# 07_SDDADC.net
KiCad netlist of a schematic drawn in Altium Designer
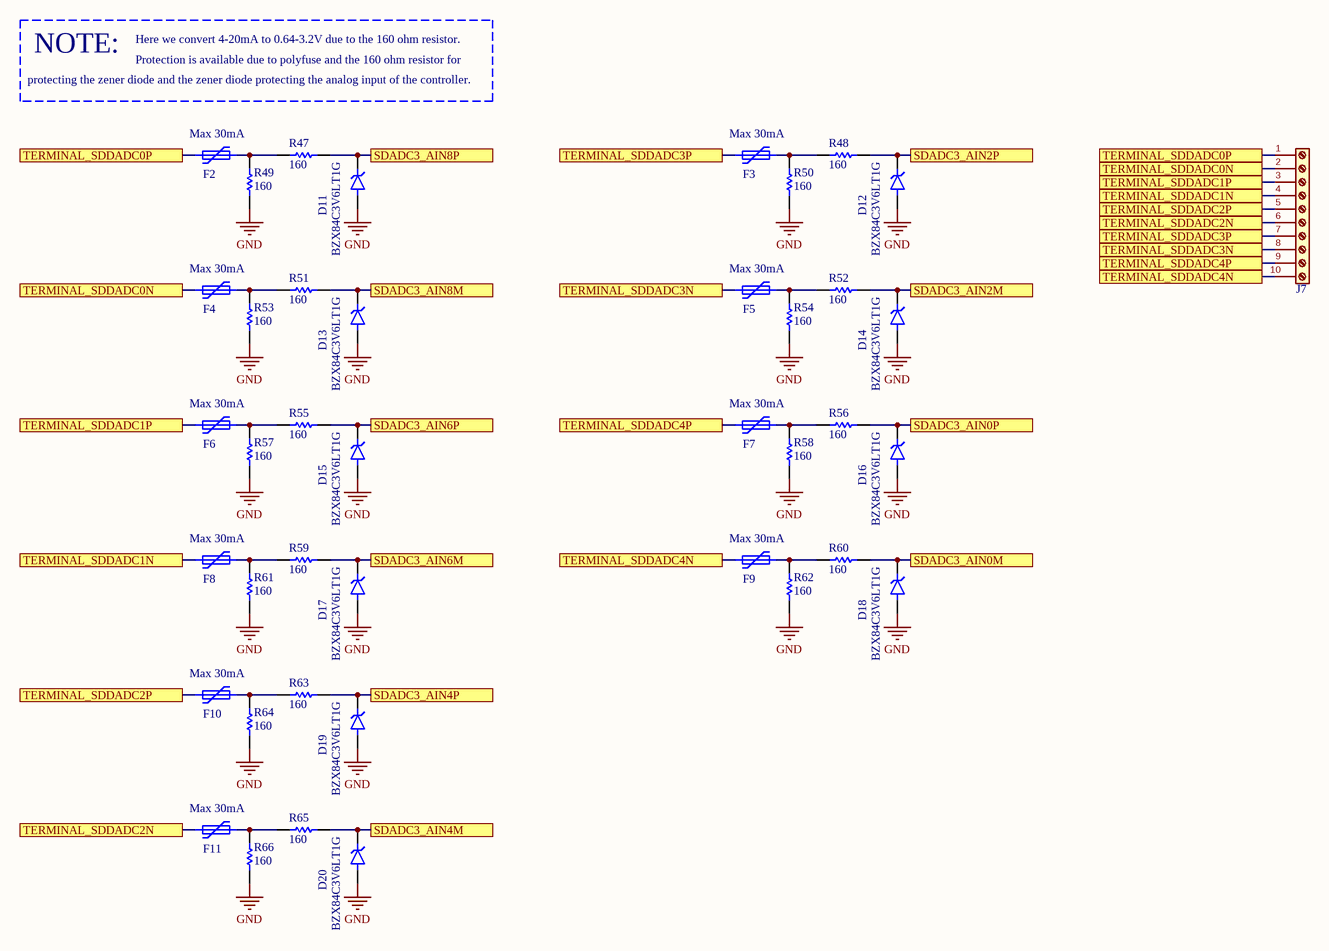
[diagram p0: 07_SDDADC.SchDoc]

(export (version "E")
  (design (tool "Eeschema 10.0.6"))
  (components
    (comp (ref "D11")
      (value "BZX84C3V6LT1G")
      (footprint "SOT95P240X111-3N")
      (fields (field (name "MP") "BZX84C10LT1G"))
      (libsource (lib "PROC051C_AWR1843BOOST_RevC") (part "BZX84C3V6LT1G"))
    )
    (comp (ref "D12")
      (value "BZX84C3V6LT1G")
      (footprint "SOT95P240X111-3N")
      (fields (field (name "MP") "BZX84C10LT1G"))
      (libsource (lib "PROC051C_AWR1843BOOST_RevC") (part "BZX84C3V6LT1G"))
    )
    (comp (ref "D13")
      (value "BZX84C3V6LT1G")
      (footprint "SOT95P240X111-3N")
      (fields (field (name "MP") "BZX84C10LT1G"))
      (libsource (lib "PROC051C_AWR1843BOOST_RevC") (part "BZX84C3V6LT1G"))
    )
    (comp (ref "D14")
      (value "BZX84C3V6LT1G")
      (footprint "SOT95P240X111-3N")
      (fields (field (name "MP") "BZX84C10LT1G"))
      (libsource (lib "PROC051C_AWR1843BOOST_RevC") (part "BZX84C3V6LT1G"))
    )
    (comp (ref "D15")
      (value "BZX84C3V6LT1G")
      (footprint "SOT95P240X111-3N")
      (fields (field (name "MP") "BZX84C10LT1G"))
      (libsource (lib "PROC051C_AWR1843BOOST_RevC") (part "BZX84C3V6LT1G"))
    )
    (comp (ref "D16")
      (value "BZX84C3V6LT1G")
      (footprint "SOT95P240X111-3N")
      (fields (field (name "MP") "BZX84C10LT1G"))
      (libsource (lib "PROC051C_AWR1843BOOST_RevC") (part "BZX84C3V6LT1G"))
    )
    (comp (ref "D17")
      (value "BZX84C3V6LT1G")
      (footprint "SOT95P240X111-3N")
      (fields (field (name "MP") "BZX84C10LT1G"))
      (libsource (lib "PROC051C_AWR1843BOOST_RevC") (part "BZX84C3V6LT1G"))
    )
    (comp (ref "D18")
      (value "BZX84C3V6LT1G")
      (footprint "SOT95P240X111-3N")
      (fields (field (name "MP") "BZX84C10LT1G"))
      (libsource (lib "PROC051C_AWR1843BOOST_RevC") (part "BZX84C3V6LT1G"))
    )
    (comp (ref "D19")
      (value "BZX84C3V6LT1G")
      (footprint "SOT95P240X111-3N")
      (fields (field (name "MP") "BZX84C10LT1G"))
      (libsource (lib "PROC051C_AWR1843BOOST_RevC") (part "BZX84C3V6LT1G"))
    )
    (comp (ref "D20")
      (value "BZX84C3V6LT1G")
      (footprint "SOT95P240X111-3N")
      (fields (field (name "MP") "BZX84C10LT1G"))
      (libsource (lib "PROC051C_AWR1843BOOST_RevC") (part "BZX84C3V6LT1G"))
    )
    (comp (ref "F2")
      (value "Max 30mA")
      (footprint "Fuse_0603_1608Metric")
      (libsource (lib "PROC051C_AWR1843BOOST_RevC") (part "Polyfuse 0603"))
    )
    (comp (ref "F3")
      (value "Max 30mA")
      (footprint "Fuse_0603_1608Metric")
      (libsource (lib "PROC051C_AWR1843BOOST_RevC") (part "Polyfuse 0603"))
    )
    (comp (ref "F4")
      (value "Max 30mA")
      (footprint "Fuse_0603_1608Metric")
      (libsource (lib "PROC051C_AWR1843BOOST_RevC") (part "Polyfuse 0603"))
    )
    (comp (ref "F5")
      (value "Max 30mA")
      (footprint "Fuse_0603_1608Metric")
      (libsource (lib "PROC051C_AWR1843BOOST_RevC") (part "Polyfuse 0603"))
    )
    (comp (ref "F6")
      (value "Max 30mA")
      (footprint "Fuse_0603_1608Metric")
      (libsource (lib "PROC051C_AWR1843BOOST_RevC") (part "Polyfuse 0603"))
    )
    (comp (ref "F7")
      (value "Max 30mA")
      (footprint "Fuse_0603_1608Metric")
      (libsource (lib "PROC051C_AWR1843BOOST_RevC") (part "Polyfuse 0603"))
    )
    (comp (ref "F8")
      (value "Max 30mA")
      (footprint "Fuse_0603_1608Metric")
      (libsource (lib "PROC051C_AWR1843BOOST_RevC") (part "Polyfuse 0603"))
    )
    (comp (ref "F9")
      (value "Max 30mA")
      (footprint "Fuse_0603_1608Metric")
      (libsource (lib "PROC051C_AWR1843BOOST_RevC") (part "Polyfuse 0603"))
    )
    (comp (ref "F10")
      (value "Max 30mA")
      (footprint "Fuse_0603_1608Metric")
      (libsource (lib "PROC051C_AWR1843BOOST_RevC") (part "Polyfuse 0603"))
    )
    (comp (ref "F11")
      (value "Max 30mA")
      (footprint "Fuse_0603_1608Metric")
      (libsource (lib "PROC051C_AWR1843BOOST_RevC") (part "Polyfuse 0603"))
    )
    (comp (ref "J7")
      (value "Terminal_01x10_P5.00")
      (footprint "TerminalBlock_Phoenix_PT-1,5-10-5.0-H_1x10_P5.00mm_Horizontal")
      (libsource (lib "PROC051C_AWR1843BOOST_RevC") (part "Terminal_01x10_P5.00"))
    )
    (comp (ref "R47")
      (value "CRCW060320R0JNEA")
      (footprint "0603")
      (description "RES, 160, 5%, 0.1 W, AEC-Q200 Grade 0, 0603")
      (fields (field (name "MANUFACTURER") "Vishay-Dale") (field (name "VALUEDISPLAYED") "160"))
      (libsource (lib "PROC051C_AWR1843BOOST_RevC") (part "RES 160R 0603"))
    )
    (comp (ref "R48")
      (value "CRCW060320R0JNEA")
      (footprint "0603")
      (description "RES, 160, 5%, 0.1 W, AEC-Q200 Grade 0, 0603")
      (fields (field (name "MANUFACTURER") "Vishay-Dale") (field (name "VALUEDISPLAYED") "160"))
      (libsource (lib "PROC051C_AWR1843BOOST_RevC") (part "RES 160R 0603"))
    )
    (comp (ref "R49")
      (value "CRCW060320R0JNEA")
      (footprint "0603")
      (description "RES, 160, 5%, 0.1 W, AEC-Q200 Grade 0, 0603")
      (fields (field (name "MANUFACTURER") "Vishay-Dale") (field (name "VALUEDISPLAYED") "160"))
      (libsource (lib "PROC051C_AWR1843BOOST_RevC") (part "RES 160R 0603"))
    )
    (comp (ref "R50")
      (value "CRCW060320R0JNEA")
      (footprint "0603")
      (description "RES, 160, 5%, 0.1 W, AEC-Q200 Grade 0, 0603")
      (fields (field (name "MANUFACTURER") "Vishay-Dale") (field (name "VALUEDISPLAYED") "160"))
      (libsource (lib "PROC051C_AWR1843BOOST_RevC") (part "RES 160R 0603"))
    )
    (comp (ref "R51")
      (value "CRCW060320R0JNEA")
      (footprint "0603")
      (description "RES, 160, 5%, 0.1 W, AEC-Q200 Grade 0, 0603")
      (fields (field (name "MANUFACTURER") "Vishay-Dale") (field (name "VALUEDISPLAYED") "160"))
      (libsource (lib "PROC051C_AWR1843BOOST_RevC") (part "RES 160R 0603"))
    )
    (comp (ref "R52")
      (value "CRCW060320R0JNEA")
      (footprint "0603")
      (description "RES, 160, 5%, 0.1 W, AEC-Q200 Grade 0, 0603")
      (fields (field (name "MANUFACTURER") "Vishay-Dale") (field (name "VALUEDISPLAYED") "160"))
      (libsource (lib "PROC051C_AWR1843BOOST_RevC") (part "RES 160R 0603"))
    )
    (comp (ref "R53")
      (value "CRCW060320R0JNEA")
      (footprint "0603")
      (description "RES, 160, 5%, 0.1 W, AEC-Q200 Grade 0, 0603")
      (fields (field (name "MANUFACTURER") "Vishay-Dale") (field (name "VALUEDISPLAYED") "160"))
      (libsource (lib "PROC051C_AWR1843BOOST_RevC") (part "RES 160R 0603"))
    )
    (comp (ref "R54")
      (value "CRCW060320R0JNEA")
      (footprint "0603")
      (description "RES, 160, 5%, 0.1 W, AEC-Q200 Grade 0, 0603")
      (fields (field (name "MANUFACTURER") "Vishay-Dale") (field (name "VALUEDISPLAYED") "160"))
      (libsource (lib "PROC051C_AWR1843BOOST_RevC") (part "RES 160R 0603"))
    )
    (comp (ref "R55")
      (value "CRCW060320R0JNEA")
      (footprint "0603")
      (description "RES, 160, 5%, 0.1 W, AEC-Q200 Grade 0, 0603")
      (fields (field (name "MANUFACTURER") "Vishay-Dale") (field (name "VALUEDISPLAYED") "160"))
      (libsource (lib "PROC051C_AWR1843BOOST_RevC") (part "RES 160R 0603"))
    )
    (comp (ref "R56")
      (value "CRCW060320R0JNEA")
      (footprint "0603")
      (description "RES, 160, 5%, 0.1 W, AEC-Q200 Grade 0, 0603")
      (fields (field (name "MANUFACTURER") "Vishay-Dale") (field (name "VALUEDISPLAYED") "160"))
      (libsource (lib "PROC051C_AWR1843BOOST_RevC") (part "RES 160R 0603"))
    )
    (comp (ref "R57")
      (value "CRCW060320R0JNEA")
      (footprint "0603")
      (description "RES, 160, 5%, 0.1 W, AEC-Q200 Grade 0, 0603")
      (fields (field (name "MANUFACTURER") "Vishay-Dale") (field (name "VALUEDISPLAYED") "160"))
      (libsource (lib "PROC051C_AWR1843BOOST_RevC") (part "RES 160R 0603"))
    )
    (comp (ref "R58")
      (value "CRCW060320R0JNEA")
      (footprint "0603")
      (description "RES, 160, 5%, 0.1 W, AEC-Q200 Grade 0, 0603")
      (fields (field (name "MANUFACTURER") "Vishay-Dale") (field (name "VALUEDISPLAYED") "160"))
      (libsource (lib "PROC051C_AWR1843BOOST_RevC") (part "RES 160R 0603"))
    )
    (comp (ref "R59")
      (value "CRCW060320R0JNEA")
      (footprint "0603")
      (description "RES, 160, 5%, 0.1 W, AEC-Q200 Grade 0, 0603")
      (fields (field (name "MANUFACTURER") "Vishay-Dale") (field (name "VALUEDISPLAYED") "160"))
      (libsource (lib "PROC051C_AWR1843BOOST_RevC") (part "RES 160R 0603"))
    )
    (comp (ref "R60")
      (value "CRCW060320R0JNEA")
      (footprint "0603")
      (description "RES, 160, 5%, 0.1 W, AEC-Q200 Grade 0, 0603")
      (fields (field (name "MANUFACTURER") "Vishay-Dale") (field (name "VALUEDISPLAYED") "160"))
      (libsource (lib "PROC051C_AWR1843BOOST_RevC") (part "RES 160R 0603"))
    )
    (comp (ref "R61")
      (value "CRCW060320R0JNEA")
      (footprint "0603")
      (description "RES, 160, 5%, 0.1 W, AEC-Q200 Grade 0, 0603")
      (fields (field (name "MANUFACTURER") "Vishay-Dale") (field (name "VALUEDISPLAYED") "160"))
      (libsource (lib "PROC051C_AWR1843BOOST_RevC") (part "RES 160R 0603"))
    )
    (comp (ref "R62")
      (value "CRCW060320R0JNEA")
      (footprint "0603")
      (description "RES, 160, 5%, 0.1 W, AEC-Q200 Grade 0, 0603")
      (fields (field (name "MANUFACTURER") "Vishay-Dale") (field (name "VALUEDISPLAYED") "160"))
      (libsource (lib "PROC051C_AWR1843BOOST_RevC") (part "RES 160R 0603"))
    )
    (comp (ref "R63")
      (value "CRCW060320R0JNEA")
      (footprint "0603")
      (description "RES, 160, 5%, 0.1 W, AEC-Q200 Grade 0, 0603")
      (fields (field (name "MANUFACTURER") "Vishay-Dale") (field (name "VALUEDISPLAYED") "160"))
      (libsource (lib "PROC051C_AWR1843BOOST_RevC") (part "RES 160R 0603"))
    )
    (comp (ref "R64")
      (value "CRCW060320R0JNEA")
      (footprint "0603")
      (description "RES, 160, 5%, 0.1 W, AEC-Q200 Grade 0, 0603")
      (fields (field (name "MANUFACTURER") "Vishay-Dale") (field (name "VALUEDISPLAYED") "160"))
      (libsource (lib "PROC051C_AWR1843BOOST_RevC") (part "RES 160R 0603"))
    )
    (comp (ref "R65")
      (value "CRCW060320R0JNEA")
      (footprint "0603")
      (description "RES, 160, 5%, 0.1 W, AEC-Q200 Grade 0, 0603")
      (fields (field (name "MANUFACTURER") "Vishay-Dale") (field (name "VALUEDISPLAYED") "160"))
      (libsource (lib "PROC051C_AWR1843BOOST_RevC") (part "RES 160R 0603"))
    )
    (comp (ref "R66")
      (value "CRCW060320R0JNEA")
      (footprint "0603")
      (description "RES, 160, 5%, 0.1 W, AEC-Q200 Grade 0, 0603")
      (fields (field (name "MANUFACTURER") "Vishay-Dale") (field (name "VALUEDISPLAYED") "160"))
      (libsource (lib "PROC051C_AWR1843BOOST_RevC") (part "RES 160R 0603"))
    )
  )
  (nets
    (net (code "1") (name "/SDADC3_AIN0M") (class "Default")
      (node (ref "D18") (pin "3") (pinfunction "K_3") (pintype "passive"))
      (node (ref "R60") (pin "2") (pinfunction "2_2") (pintype "passive"))
    )
    (net (code "2") (name "/SDADC3_AIN0P") (class "Default")
      (node (ref "D16") (pin "3") (pinfunction "K_3") (pintype "passive"))
      (node (ref "R56") (pin "2") (pinfunction "2_2") (pintype "passive"))
    )
    (net (code "3") (name "/SDADC3_AIN2M") (class "Default")
      (node (ref "D14") (pin "3") (pinfunction "K_3") (pintype "passive"))
      (node (ref "R52") (pin "2") (pinfunction "2_2") (pintype "passive"))
    )
    (net (code "4") (name "/SDADC3_AIN2P") (class "Default")
      (node (ref "D12") (pin "3") (pinfunction "K_3") (pintype "passive"))
      (node (ref "R48") (pin "2") (pinfunction "2_2") (pintype "passive"))
    )
    (net (code "5") (name "/SDADC3_AIN4M") (class "Default")
      (node (ref "D20") (pin "3") (pinfunction "K_3") (pintype "passive"))
      (node (ref "R65") (pin "2") (pinfunction "2_2") (pintype "passive"))
    )
    (net (code "6") (name "/SDADC3_AIN4P") (class "Default")
      (node (ref "D19") (pin "3") (pinfunction "K_3") (pintype "passive"))
      (node (ref "R63") (pin "2") (pinfunction "2_2") (pintype "passive"))
    )
    (net (code "7") (name "/SDADC3_AIN6M") (class "Default")
      (node (ref "D17") (pin "3") (pinfunction "K_3") (pintype "passive"))
      (node (ref "R59") (pin "2") (pinfunction "2_2") (pintype "passive"))
    )
    (net (code "8") (name "/SDADC3_AIN6P") (class "Default")
      (node (ref "D15") (pin "3") (pinfunction "K_3") (pintype "passive"))
      (node (ref "R55") (pin "2") (pinfunction "2_2") (pintype "passive"))
    )
    (net (code "9") (name "/SDADC3_AIN8M") (class "Default")
      (node (ref "D13") (pin "3") (pinfunction "K_3") (pintype "passive"))
      (node (ref "R51") (pin "2") (pinfunction "2_2") (pintype "passive"))
    )
    (net (code "10") (name "/SDADC3_AIN8P") (class "Default")
      (node (ref "D11") (pin "3") (pinfunction "K_3") (pintype "passive"))
      (node (ref "R47") (pin "2") (pinfunction "2_2") (pintype "passive"))
    )
    (net (code "11") (name "/TERMINAL_SDDADC0N") (class "Default")
      (node (ref "F4") (pin "1") (pinfunction "1_1") (pintype "passive"))
      (node (ref "J7") (pin "2") (pinfunction "Pin_2_2") (pintype "passive"))
    )
    (net (code "12") (name "/TERMINAL_SDDADC0P") (class "Default")
      (node (ref "F2") (pin "1") (pinfunction "1_1") (pintype "passive"))
      (node (ref "J7") (pin "1") (pinfunction "Pin_1_1") (pintype "passive"))
    )
    (net (code "13") (name "/TERMINAL_SDDADC1N") (class "Default")
      (node (ref "F8") (pin "1") (pinfunction "1_1") (pintype "passive"))
      (node (ref "J7") (pin "4") (pinfunction "Pin_4_4") (pintype "passive"))
    )
    (net (code "14") (name "/TERMINAL_SDDADC1P") (class "Default")
      (node (ref "F6") (pin "1") (pinfunction "1_1") (pintype "passive"))
      (node (ref "J7") (pin "3") (pinfunction "Pin_3_3") (pintype "passive"))
    )
    (net (code "15") (name "/TERMINAL_SDDADC2N") (class "Default")
      (node (ref "F11") (pin "1") (pinfunction "1_1") (pintype "passive"))
      (node (ref "J7") (pin "6") (pinfunction "Pin_6_6") (pintype "passive"))
    )
    (net (code "16") (name "/TERMINAL_SDDADC2P") (class "Default")
      (node (ref "F10") (pin "1") (pinfunction "1_1") (pintype "passive"))
      (node (ref "J7") (pin "5") (pinfunction "Pin_5_5") (pintype "passive"))
    )
    (net (code "17") (name "/TERMINAL_SDDADC3N") (class "Default")
      (node (ref "F5") (pin "1") (pinfunction "1_1") (pintype "passive"))
      (node (ref "J7") (pin "8") (pinfunction "Pin_8_8") (pintype "passive"))
    )
    (net (code "18") (name "/TERMINAL_SDDADC3P") (class "Default")
      (node (ref "F3") (pin "1") (pinfunction "1_1") (pintype "passive"))
      (node (ref "J7") (pin "7") (pinfunction "Pin_7_7") (pintype "passive"))
    )
    (net (code "19") (name "/TERMINAL_SDDADC4N") (class "Default")
      (node (ref "F9") (pin "1") (pinfunction "1_1") (pintype "passive"))
      (node (ref "J7") (pin "10") (pinfunction "Pin_10_10") (pintype "passive"))
    )
    (net (code "20") (name "/TERMINAL_SDDADC4P") (class "Default")
      (node (ref "F7") (pin "1") (pinfunction "1_1") (pintype "passive"))
      (node (ref "J7") (pin "9") (pinfunction "Pin_9_9") (pintype "passive"))
    )
    (net (code "21") (name "GND") (class "Default")
      (node (ref "D11") (pin "1") (pinfunction "A_1") (pintype "passive"))
      (node (ref "D12") (pin "1") (pinfunction "A_1") (pintype "passive"))
      (node (ref "D13") (pin "1") (pinfunction "A_1") (pintype "passive"))
      (node (ref "D14") (pin "1") (pinfunction "A_1") (pintype "passive"))
      (node (ref "D15") (pin "1") (pinfunction "A_1") (pintype "passive"))
      (node (ref "D16") (pin "1") (pinfunction "A_1") (pintype "passive"))
      (node (ref "D17") (pin "1") (pinfunction "A_1") (pintype "passive"))
      (node (ref "D18") (pin "1") (pinfunction "A_1") (pintype "passive"))
      (node (ref "D19") (pin "1") (pinfunction "A_1") (pintype "passive"))
      (node (ref "D20") (pin "1") (pinfunction "A_1") (pintype "passive"))
      (node (ref "R49") (pin "1") (pinfunction "1_1") (pintype "passive"))
      (node (ref "R50") (pin "1") (pinfunction "1_1") (pintype "passive"))
      (node (ref "R53") (pin "1") (pinfunction "1_1") (pintype "passive"))
      (node (ref "R54") (pin "1") (pinfunction "1_1") (pintype "passive"))
      (node (ref "R57") (pin "1") (pinfunction "1_1") (pintype "passive"))
      (node (ref "R58") (pin "1") (pinfunction "1_1") (pintype "passive"))
      (node (ref "R61") (pin "1") (pinfunction "1_1") (pintype "passive"))
      (node (ref "R62") (pin "1") (pinfunction "1_1") (pintype "passive"))
      (node (ref "R64") (pin "1") (pinfunction "1_1") (pintype "passive"))
      (node (ref "R66") (pin "1") (pinfunction "1_1") (pintype "passive"))
    )
    (net (code "22") (name "Net-(F2-Pad2)") (class "Default")
      (node (ref "F2") (pin "2") (pinfunction "2_2") (pintype "passive"))
      (node (ref "R47") (pin "1") (pinfunction "1_1") (pintype "passive"))
      (node (ref "R49") (pin "2") (pinfunction "2_2") (pintype "passive"))
    )
    (net (code "23") (name "Net-(F3-Pad2)") (class "Default")
      (node (ref "F3") (pin "2") (pinfunction "2_2") (pintype "passive"))
      (node (ref "R48") (pin "1") (pinfunction "1_1") (pintype "passive"))
      (node (ref "R50") (pin "2") (pinfunction "2_2") (pintype "passive"))
    )
    (net (code "24") (name "Net-(F4-Pad2)") (class "Default")
      (node (ref "F4") (pin "2") (pinfunction "2_2") (pintype "passive"))
      (node (ref "R51") (pin "1") (pinfunction "1_1") (pintype "passive"))
      (node (ref "R53") (pin "2") (pinfunction "2_2") (pintype "passive"))
    )
    (net (code "25") (name "Net-(F5-Pad2)") (class "Default")
      (node (ref "F5") (pin "2") (pinfunction "2_2") (pintype "passive"))
      (node (ref "R52") (pin "1") (pinfunction "1_1") (pintype "passive"))
      (node (ref "R54") (pin "2") (pinfunction "2_2") (pintype "passive"))
    )
    (net (code "26") (name "Net-(F6-Pad2)") (class "Default")
      (node (ref "F6") (pin "2") (pinfunction "2_2") (pintype "passive"))
      (node (ref "R55") (pin "1") (pinfunction "1_1") (pintype "passive"))
      (node (ref "R57") (pin "2") (pinfunction "2_2") (pintype "passive"))
    )
    (net (code "27") (name "Net-(F7-Pad2)") (class "Default")
      (node (ref "F7") (pin "2") (pinfunction "2_2") (pintype "passive"))
      (node (ref "R56") (pin "1") (pinfunction "1_1") (pintype "passive"))
      (node (ref "R58") (pin "2") (pinfunction "2_2") (pintype "passive"))
    )
    (net (code "28") (name "Net-(F8-Pad2)") (class "Default")
      (node (ref "F8") (pin "2") (pinfunction "2_2") (pintype "passive"))
      (node (ref "R59") (pin "1") (pinfunction "1_1") (pintype "passive"))
      (node (ref "R61") (pin "2") (pinfunction "2_2") (pintype "passive"))
    )
    (net (code "29") (name "Net-(F9-Pad2)") (class "Default")
      (node (ref "F9") (pin "2") (pinfunction "2_2") (pintype "passive"))
      (node (ref "R60") (pin "1") (pinfunction "1_1") (pintype "passive"))
      (node (ref "R62") (pin "2") (pinfunction "2_2") (pintype "passive"))
    )
    (net (code "30") (name "Net-(F10-Pad2)") (class "Default")
      (node (ref "F10") (pin "2") (pinfunction "2_2") (pintype "passive"))
      (node (ref "R63") (pin "1") (pinfunction "1_1") (pintype "passive"))
      (node (ref "R64") (pin "2") (pinfunction "2_2") (pintype "passive"))
    )
    (net (code "31") (name "Net-(F11-Pad2)") (class "Default")
      (node (ref "F11") (pin "2") (pinfunction "2_2") (pintype "passive"))
      (node (ref "R65") (pin "1") (pinfunction "1_1") (pintype "passive"))
      (node (ref "R66") (pin "2") (pinfunction "2_2") (pintype "passive"))
    )
  )
)
